# pc-bus.net
KiCad netlist of a schematic drawn in EAGLE
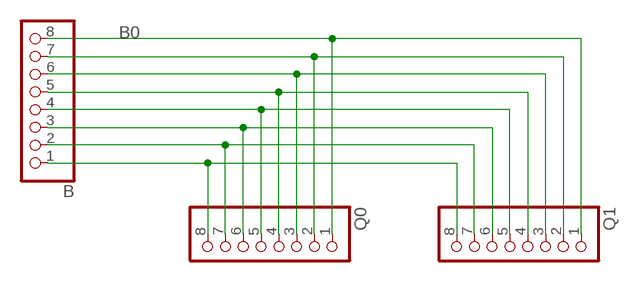
[diagram p0: schematic, sheet 1]

(export (version "E")
  (design (tool "Eeschema 10.0.6"))
  (components
    (comp (ref "B")
      (value "PINHD-1X8")
      (footprint "eagle-import:1X08")
      (libsource (lib "eagle-import") (part "PINHD-1X8"))
    )
    (comp (ref "Q0")
      (value "PINHD-1X8")
      (footprint "eagle-import:1X08")
      (libsource (lib "eagle-import") (part "PINHD-1X8"))
    )
    (comp (ref "Q1")
      (value "PINHD-1X8")
      (footprint "eagle-import:1X08")
      (libsource (lib "eagle-import") (part "PINHD-1X8"))
    )
  )
  (nets
    (net (code "1") (name "/B0") (class "Default")
      (node (ref "B") (pin "8") (pinfunction "8_8") (pintype "passive"))
      (node (ref "Q0") (pin "1") (pinfunction "1_1") (pintype "passive"))
      (node (ref "Q1") (pin "1") (pinfunction "1_1") (pintype "passive"))
    )
    (net (code "2") (name "Net-(B-Pad1)") (class "Default")
      (node (ref "B") (pin "1") (pinfunction "1_1") (pintype "passive"))
      (node (ref "Q0") (pin "8") (pinfunction "8_8") (pintype "passive"))
      (node (ref "Q1") (pin "8") (pinfunction "8_8") (pintype "passive"))
    )
    (net (code "3") (name "Net-(B-Pad2)") (class "Default")
      (node (ref "B") (pin "2") (pinfunction "2_2") (pintype "passive"))
      (node (ref "Q0") (pin "7") (pinfunction "7_7") (pintype "passive"))
      (node (ref "Q1") (pin "7") (pinfunction "7_7") (pintype "passive"))
    )
    (net (code "4") (name "Net-(B-Pad3)") (class "Default")
      (node (ref "B") (pin "3") (pinfunction "3_3") (pintype "passive"))
      (node (ref "Q0") (pin "6") (pinfunction "6_6") (pintype "passive"))
      (node (ref "Q1") (pin "6") (pinfunction "6_6") (pintype "passive"))
    )
    (net (code "5") (name "Net-(B-Pad4)") (class "Default")
      (node (ref "B") (pin "4") (pinfunction "4_4") (pintype "passive"))
      (node (ref "Q0") (pin "5") (pinfunction "5_5") (pintype "passive"))
      (node (ref "Q1") (pin "5") (pinfunction "5_5") (pintype "passive"))
    )
    (net (code "6") (name "Net-(B-Pad5)") (class "Default")
      (node (ref "B") (pin "5") (pinfunction "5_5") (pintype "passive"))
      (node (ref "Q0") (pin "4") (pinfunction "4_4") (pintype "passive"))
      (node (ref "Q1") (pin "4") (pinfunction "4_4") (pintype "passive"))
    )
    (net (code "7") (name "Net-(B-Pad6)") (class "Default")
      (node (ref "B") (pin "6") (pinfunction "6_6") (pintype "passive"))
      (node (ref "Q0") (pin "3") (pinfunction "3_3") (pintype "passive"))
      (node (ref "Q1") (pin "3") (pinfunction "3_3") (pintype "passive"))
    )
    (net (code "8") (name "Net-(B-Pad7)") (class "Default")
      (node (ref "B") (pin "7") (pinfunction "7_7") (pintype "passive"))
      (node (ref "Q0") (pin "2") (pinfunction "2_2") (pintype "passive"))
      (node (ref "Q1") (pin "2") (pinfunction "2_2") (pintype "passive"))
    )
  )
)
